# Startracker_Stepper.net
KiCad netlist of a schematic drawn in Altium Designer
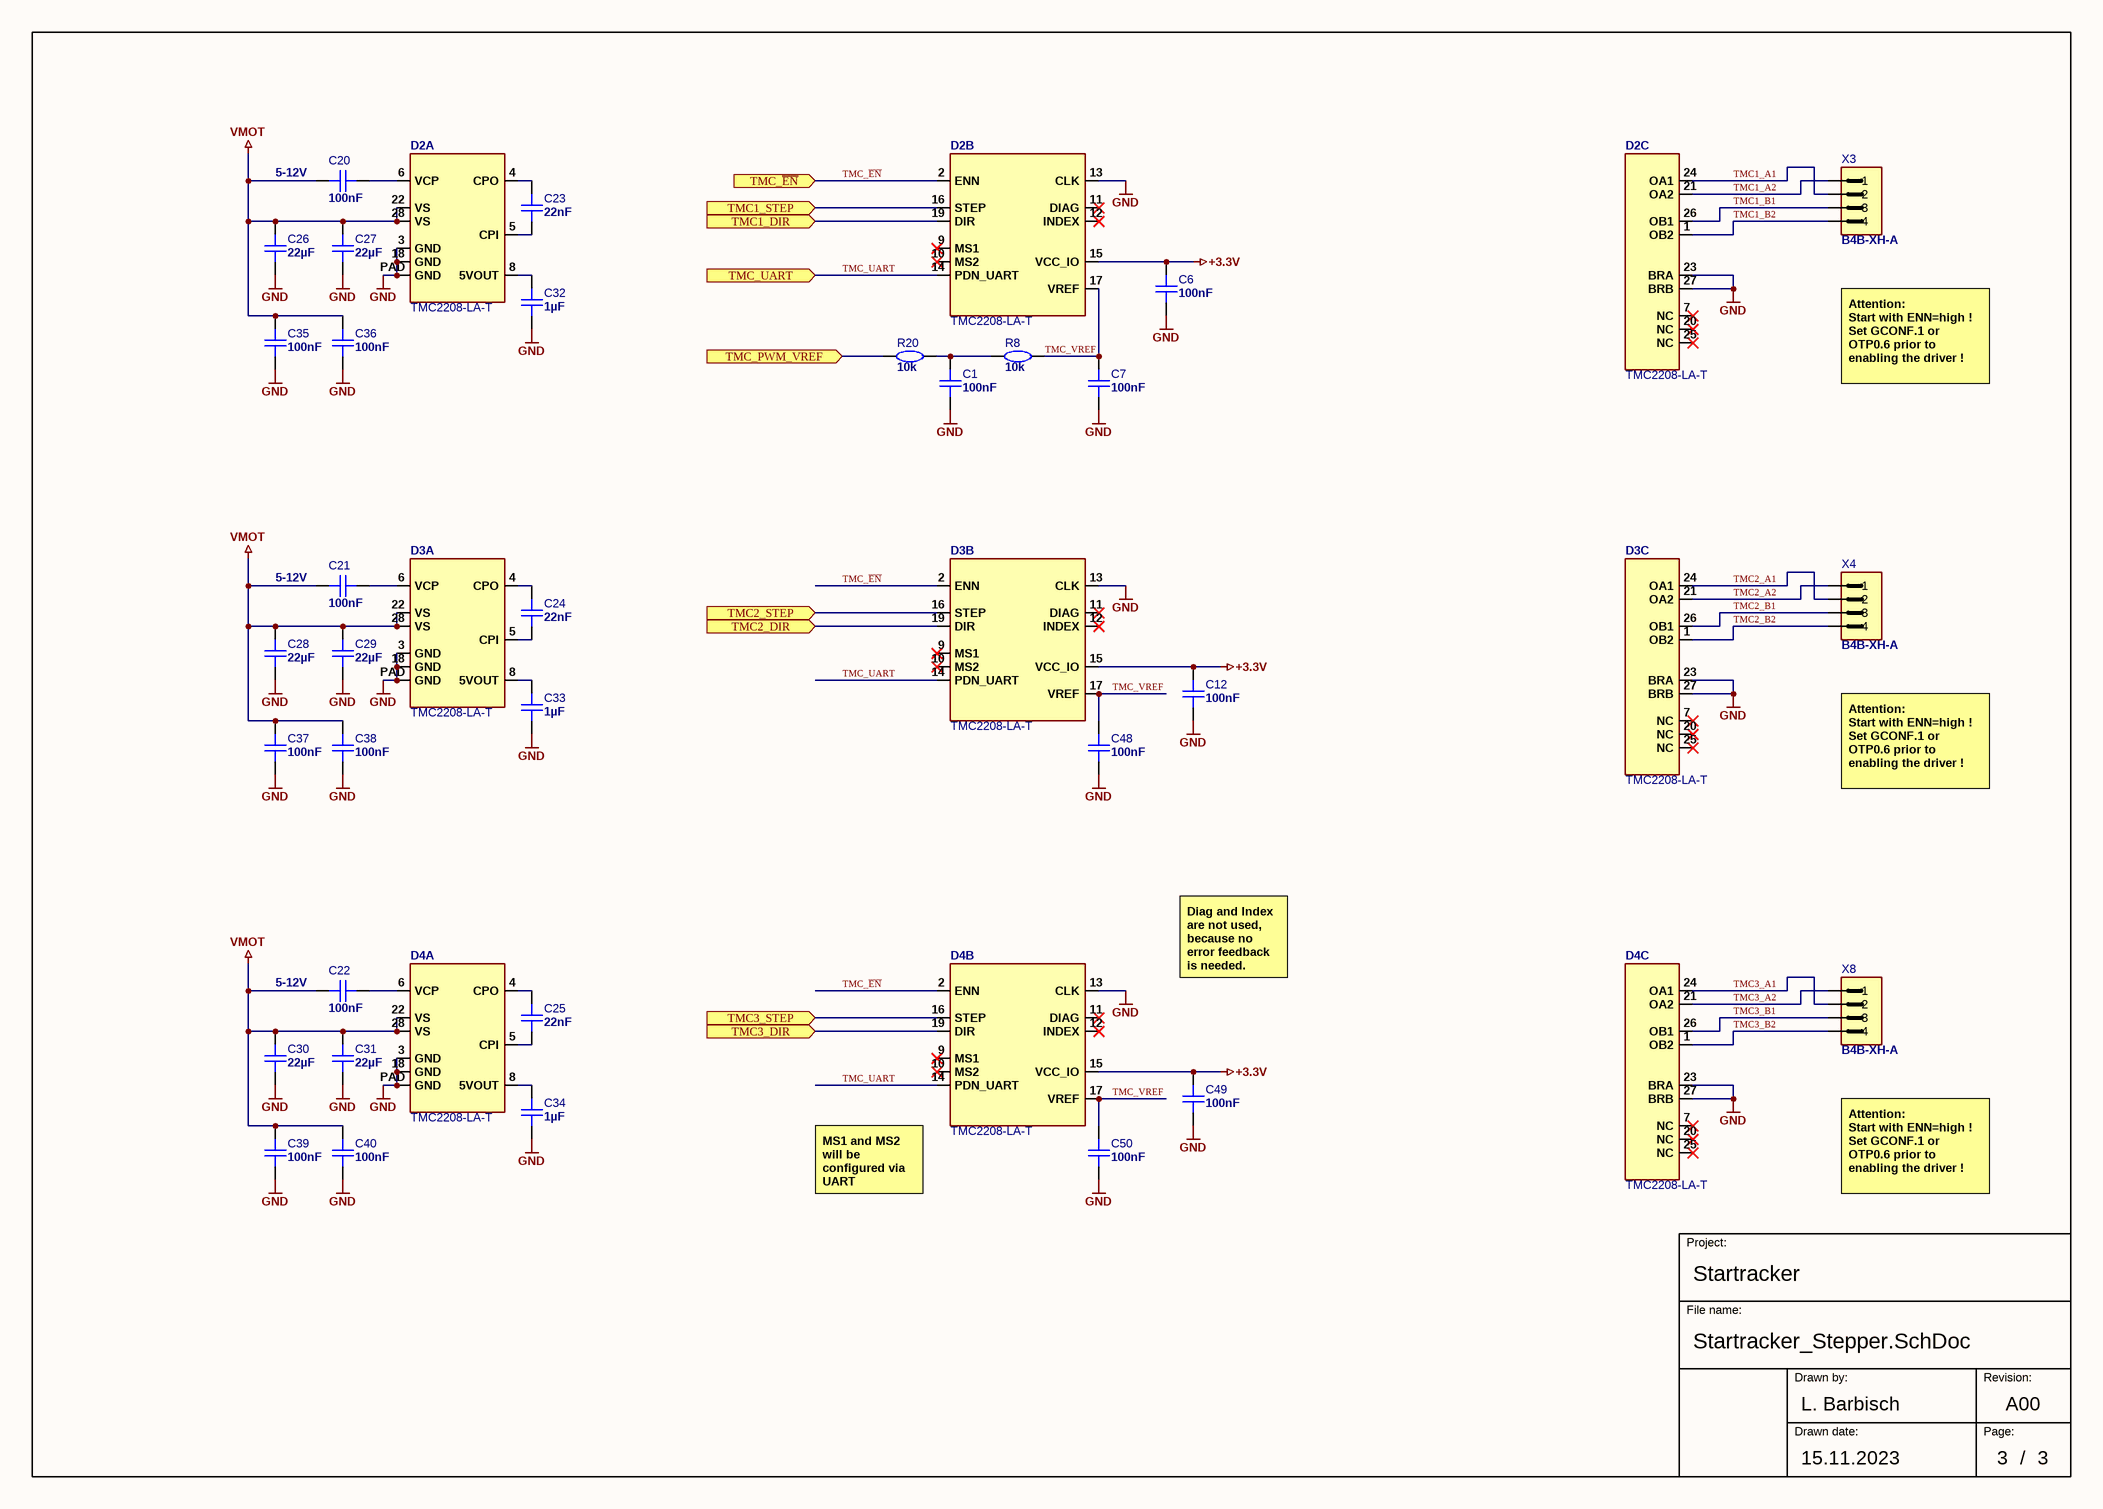
[diagram p0: Startracker_Stepper.SchDoc]

(export (version "E")
  (design (tool "Eeschema 10.0.6"))
  (components
    (comp (ref "C1")
      (value "100nF")
      (footprint "C-0603_1608_095_L_RF")
      (description "Cap Cer SMD 100n 50V 10% 0603 X7R")
      (fields
        (field (name "MANUFACTURER") "KEMET")
        (field (name "MANUFACTURER PART NUMBER") "C0603C104K5RAC")
        (field (name "USER") "epph")
      )
      (libsource (lib "GPV Switzerland SA") (part "CAP"))
    )
    (comp (ref "C6")
      (value "100nF")
      (footprint "C-0603_1608_095_L_RF")
      (description "Cap Cer SMD 100n 50V 10% 0603 X7R")
      (fields
        (field (name "MANUFACTURER") "KEMET")
        (field (name "MANUFACTURER PART NUMBER") "C0603C104K5RAC")
        (field (name "USER") "epph")
      )
      (libsource (lib "GPV Switzerland SA") (part "CAP"))
    )
    (comp (ref "C7")
      (value "100nF")
      (footprint "C-0603_1608_095_L_RF")
      (description "Cap Cer SMD 100n 50V 10% 0603 X7R")
      (fields
        (field (name "MANUFACTURER") "KEMET")
        (field (name "MANUFACTURER PART NUMBER") "C0603C104K5RAC")
        (field (name "USER") "epph")
      )
      (libsource (lib "GPV Switzerland SA") (part "CAP"))
    )
    (comp (ref "C12")
      (value "100nF")
      (footprint "C-0603_1608_095_L_RF")
      (description "Cap Cer SMD 100n 50V 10% 0603 X7R")
      (fields
        (field (name "MANUFACTURER") "KEMET")
        (field (name "MANUFACTURER PART NUMBER") "C0603C104K5RAC")
        (field (name "USER") "epph")
      )
      (libsource (lib "GPV Switzerland SA") (part "CAP"))
    )
    (comp (ref "C20")
      (value "100nF")
      (footprint "C-0603_1608_095_L_RF")
      (description "Cap Cer SMD 100n 50V 10% 0603 X7R")
      (fields
        (field (name "MANUFACTURER") "KEMET")
        (field (name "MANUFACTURER PART NUMBER") "C0603C104K5RAC")
        (field (name "USER") "epph")
      )
      (libsource (lib "GPV Switzerland SA") (part "CAP"))
    )
    (comp (ref "C21")
      (value "100nF")
      (footprint "C-0603_1608_095_L_RF")
      (description "Cap Cer SMD 100n 50V 10% 0603 X7R")
      (fields
        (field (name "MANUFACTURER") "KEMET")
        (field (name "MANUFACTURER PART NUMBER") "C0603C104K5RAC")
        (field (name "USER") "epph")
      )
      (libsource (lib "GPV Switzerland SA") (part "CAP"))
    )
    (comp (ref "C22")
      (value "100nF")
      (footprint "C-0603_1608_095_L_RF")
      (description "Cap Cer SMD 100n 50V 10% 0603 X7R")
      (fields
        (field (name "MANUFACTURER") "KEMET")
        (field (name "MANUFACTURER PART NUMBER") "C0603C104K5RAC")
        (field (name "USER") "epph")
      )
      (libsource (lib "GPV Switzerland SA") (part "CAP"))
    )
    (comp (ref "C23")
      (value "22nF")
      (footprint "C-0603_1608_095_L_RF")
      (description "Cap Cer SMD 22n 50V 10% 0603 X7R")
      (fields
        (field (name "MANUFACTURER PART NUMBER") "06035C223KAT*")
        (field (name "MANUFACTURER") "AVX")
        (field (name "USER") "zupa")
      )
      (libsource (lib "GPV Switzerland SA") (part "CAP"))
    )
    (comp (ref "C24")
      (value "22nF")
      (footprint "C-0603_1608_095_L_RF")
      (description "Cap Cer SMD 22n 50V 10% 0603 X7R")
      (fields
        (field (name "MANUFACTURER PART NUMBER") "06035C223KAT*")
        (field (name "MANUFACTURER") "AVX")
        (field (name "USER") "zupa")
      )
      (libsource (lib "GPV Switzerland SA") (part "CAP"))
    )
    (comp (ref "C25")
      (value "22nF")
      (footprint "C-0603_1608_095_L_RF")
      (description "Cap Cer SMD 22n 50V 10% 0603 X7R")
      (fields
        (field (name "MANUFACTURER PART NUMBER") "06035C223KAT*")
        (field (name "MANUFACTURER") "AVX")
        (field (name "USER") "zupa")
      )
      (libsource (lib "GPV Switzerland SA") (part "CAP"))
    )
    (comp (ref "C26")
      (value "22µF")
      (footprint "C-1206_3216_230_L_RF")
      (description "Cap Cer SMD 22u 25V 10% 1206 X5R")
      (fields
        (field (name "MANUFACTURER PART NUMBER") "GRM31CR61E226KE15*")
        (field (name "MANUFACTURER") "MURATA")
        (field (name "USER") "zupa")
      )
      (libsource (lib "GPV Switzerland SA") (part "CAP"))
    )
    (comp (ref "C27")
      (value "22µF")
      (footprint "C-1206_3216_230_L_RF")
      (description "Cap Cer SMD 22u 25V 10% 1206 X5R")
      (fields
        (field (name "MANUFACTURER PART NUMBER") "GRM31CR61E226KE15*")
        (field (name "MANUFACTURER") "MURATA")
        (field (name "USER") "zupa")
      )
      (libsource (lib "GPV Switzerland SA") (part "CAP"))
    )
    (comp (ref "C28")
      (value "22µF")
      (footprint "C-1206_3216_230_L_RF")
      (description "Cap Cer SMD 22u 25V 10% 1206 X5R")
      (fields
        (field (name "MANUFACTURER PART NUMBER") "GRM31CR61E226KE15*")
        (field (name "MANUFACTURER") "MURATA")
        (field (name "USER") "zupa")
      )
      (libsource (lib "GPV Switzerland SA") (part "CAP"))
    )
    (comp (ref "C29")
      (value "22µF")
      (footprint "C-1206_3216_230_L_RF")
      (description "Cap Cer SMD 22u 25V 10% 1206 X5R")
      (fields
        (field (name "MANUFACTURER PART NUMBER") "GRM31CR61E226KE15*")
        (field (name "MANUFACTURER") "MURATA")
        (field (name "USER") "zupa")
      )
      (libsource (lib "GPV Switzerland SA") (part "CAP"))
    )
    (comp (ref "C30")
      (value "22µF")
      (footprint "C-1206_3216_230_L_RF")
      (description "Cap Cer SMD 22u 25V 10% 1206 X5R")
      (fields
        (field (name "MANUFACTURER PART NUMBER") "GRM31CR61E226KE15*")
        (field (name "MANUFACTURER") "MURATA")
        (field (name "USER") "zupa")
      )
      (libsource (lib "GPV Switzerland SA") (part "CAP"))
    )
    (comp (ref "C31")
      (value "22µF")
      (footprint "C-1206_3216_230_L_RF")
      (description "Cap Cer SMD 22u 25V 10% 1206 X5R")
      (fields
        (field (name "MANUFACTURER PART NUMBER") "GRM31CR61E226KE15*")
        (field (name "MANUFACTURER") "MURATA")
        (field (name "USER") "zupa")
      )
      (libsource (lib "GPV Switzerland SA") (part "CAP"))
    )
    (comp (ref "C32")
      (value "1µF")
      (footprint "C-0603_1608_095_L_RF")
      (description "Cap Cer SMD 1u 16V 10% 0603 X7R")
      (fields
        (field (name "MANUFACTURER PART NUMBER") "0603YC105KAT*")
        (field (name "MANUFACTURER") "AVX")
        (field (name "USER") "zupa")
      )
      (libsource (lib "GPV Switzerland SA") (part "CAP"))
    )
    (comp (ref "C33")
      (value "1µF")
      (footprint "C-0603_1608_095_L_RF")
      (description "Cap Cer SMD 1u 16V 10% 0603 X7R")
      (fields
        (field (name "MANUFACTURER PART NUMBER") "0603YC105KAT*")
        (field (name "MANUFACTURER") "AVX")
        (field (name "USER") "zupa")
      )
      (libsource (lib "GPV Switzerland SA") (part "CAP"))
    )
    (comp (ref "C34")
      (value "1µF")
      (footprint "C-0603_1608_095_L_RF")
      (description "Cap Cer SMD 1u 16V 10% 0603 X7R")
      (fields
        (field (name "MANUFACTURER PART NUMBER") "0603YC105KAT*")
        (field (name "MANUFACTURER") "AVX")
        (field (name "USER") "zupa")
      )
      (libsource (lib "GPV Switzerland SA") (part "CAP"))
    )
    (comp (ref "C35")
      (value "100nF")
      (footprint "C-0603_1608_095_L_RF")
      (description "Cap Cer SMD 100n 50V 10% 0603 X7R")
      (fields
        (field (name "MANUFACTURER") "KEMET")
        (field (name "MANUFACTURER PART NUMBER") "C0603C104K5RAC")
        (field (name "USER") "epph")
      )
      (libsource (lib "GPV Switzerland SA") (part "CAP"))
    )
    (comp (ref "C36")
      (value "100nF")
      (footprint "C-0603_1608_095_L_RF")
      (description "Cap Cer SMD 100n 50V 10% 0603 X7R")
      (fields
        (field (name "MANUFACTURER") "KEMET")
        (field (name "MANUFACTURER PART NUMBER") "C0603C104K5RAC")
        (field (name "USER") "epph")
      )
      (libsource (lib "GPV Switzerland SA") (part "CAP"))
    )
    (comp (ref "C37")
      (value "100nF")
      (footprint "C-0603_1608_095_L_RF")
      (description "Cap Cer SMD 100n 50V 10% 0603 X7R")
      (fields
        (field (name "MANUFACTURER") "KEMET")
        (field (name "MANUFACTURER PART NUMBER") "C0603C104K5RAC")
        (field (name "USER") "epph")
      )
      (libsource (lib "GPV Switzerland SA") (part "CAP"))
    )
    (comp (ref "C38")
      (value "100nF")
      (footprint "C-0603_1608_095_L_RF")
      (description "Cap Cer SMD 100n 50V 10% 0603 X7R")
      (fields
        (field (name "MANUFACTURER") "KEMET")
        (field (name "MANUFACTURER PART NUMBER") "C0603C104K5RAC")
        (field (name "USER") "epph")
      )
      (libsource (lib "GPV Switzerland SA") (part "CAP"))
    )
    (comp (ref "C39")
      (value "100nF")
      (footprint "C-0603_1608_095_L_RF")
      (description "Cap Cer SMD 100n 50V 10% 0603 X7R")
      (fields
        (field (name "MANUFACTURER") "KEMET")
        (field (name "MANUFACTURER PART NUMBER") "C0603C104K5RAC")
        (field (name "USER") "epph")
      )
      (libsource (lib "GPV Switzerland SA") (part "CAP"))
    )
    (comp (ref "C40")
      (value "100nF")
      (footprint "C-0603_1608_095_L_RF")
      (description "Cap Cer SMD 100n 50V 10% 0603 X7R")
      (fields
        (field (name "MANUFACTURER") "KEMET")
        (field (name "MANUFACTURER PART NUMBER") "C0603C104K5RAC")
        (field (name "USER") "epph")
      )
      (libsource (lib "GPV Switzerland SA") (part "CAP"))
    )
    (comp (ref "C48")
      (value "100nF")
      (footprint "C-0603_1608_095_L_RF")
      (description "Cap Cer SMD 100n 50V 10% 0603 X7R")
      (fields
        (field (name "MANUFACTURER") "KEMET")
        (field (name "MANUFACTURER PART NUMBER") "C0603C104K5RAC")
        (field (name "USER") "epph")
      )
      (libsource (lib "GPV Switzerland SA") (part "CAP"))
    )
    (comp (ref "C49")
      (value "100nF")
      (footprint "C-0603_1608_095_L_RF")
      (description "Cap Cer SMD 100n 50V 10% 0603 X7R")
      (fields
        (field (name "MANUFACTURER") "KEMET")
        (field (name "MANUFACTURER PART NUMBER") "C0603C104K5RAC")
        (field (name "USER") "epph")
      )
      (libsource (lib "GPV Switzerland SA") (part "CAP"))
    )
    (comp (ref "C50")
      (value "100nF")
      (footprint "C-0603_1608_095_L_RF")
      (description "Cap Cer SMD 100n 50V 10% 0603 X7R")
      (fields
        (field (name "MANUFACTURER") "KEMET")
        (field (name "MANUFACTURER PART NUMBER") "C0603C104K5RAC")
        (field (name "USER") "epph")
      )
      (libsource (lib "GPV Switzerland SA") (part "CAP"))
    )
    (comp (ref "D2")
      (value "TMC2208-LA-T")
      (footprint "QFN28_N_RF")
      (description "IC DRIVER Stepper 1.4A")
      (fields (field (name "MANUFACTURER") "Analog Devices"))
      (libsource (lib "Global Library") (part "TMC2208-LA-T"))
    )
    (comp (ref "D3")
      (value "TMC2208-LA-T")
      (footprint "QFN28_N_RF")
      (description "IC DRIVER Stepper 1.4A")
      (fields (field (name "MANUFACTURER") "Analog Devices"))
      (libsource (lib "Global Library") (part "TMC2208-LA-T"))
    )
    (comp (ref "D4")
      (value "TMC2208-LA-T")
      (footprint "QFN28_N_RF")
      (description "IC DRIVER Stepper 1.4A")
      (fields (field (name "MANUFACTURER") "Analog Devices"))
      (libsource (lib "Global Library") (part "TMC2208-LA-T"))
    )
    (comp (ref "R8")
      (value "10k")
      (footprint "R-0603_1608_050_L_RF")
      (description "Res SMD 10k 1% 0.1W 0603")
      (fields
        (field (name "MANUFACTURER") "YAGEO")
        (field (name "MANUFACTURER PART NUMBER") "RC0603FR-0710KL")
        (field (name "USER") "zupa")
      )
      (libsource (lib "GPV Switzerland SA") (part "RES"))
    )
    (comp (ref "R20")
      (value "10k")
      (footprint "R-0603_1608_050_L_RF")
      (description "Res SMD 10k 1% 0.1W 0603")
      (fields
        (field (name "MANUFACTURER") "YAGEO")
        (field (name "MANUFACTURER PART NUMBER") "RC0603FR-0710KL")
        (field (name "USER") "zupa")
      )
      (libsource (lib "GPV Switzerland SA") (part "RES"))
    )
    (comp (ref "X3")
      (value "B4B-XH-A")
      (footprint "X-0124X0057-R_M04_P0250_JST_B4B-XH-A")
      (description "CONN HEADER  4POS_JST_B4B-XH")
      (fields
        (field (name "MANUFACTURER") "JST")
        (field (name "Comment") "CONN HEADER XH 4POS THT")
        (field (name "USER") "balu")
      )
      (libsource (lib "GPV Switzerland SA") (part "Connector-4P"))
    )
    (comp (ref "X4")
      (value "B4B-XH-A")
      (footprint "X-0124X0057-R_M04_P0250_JST_B4B-XH-A")
      (description "CONN HEADER  4POS_JST_B4B-XH")
      (fields
        (field (name "MANUFACTURER") "JST")
        (field (name "Comment") "CONN HEADER XH 4POS THT")
        (field (name "USER") "balu")
      )
      (libsource (lib "GPV Switzerland SA") (part "Connector-4P"))
    )
    (comp (ref "X8")
      (value "B4B-XH-A")
      (footprint "X-0124X0057-R_M04_P0250_JST_B4B-XH-A")
      (description "CONN HEADER  4POS_JST_B4B-XH")
      (fields
        (field (name "MANUFACTURER") "JST")
        (field (name "Comment") "CONN HEADER XH 4POS THT")
        (field (name "USER") "balu")
      )
      (libsource (lib "GPV Switzerland SA") (part "Connector-4P"))
    )
  )
  (nets
    (net (code "1") (name "+3.3V") (class "Default")
      (node (ref "C12") (pin "1") (pinfunction "1_1") (pintype "passive"))
      (node (ref "C49") (pin "1") (pinfunction "1_1") (pintype "passive"))
      (node (ref "C6") (pin "1") (pinfunction "1_1") (pintype "passive"))
      (node (ref "D2") (pin "15") (pinfunction "VCC_IO_15") (pintype "passive"))
      (node (ref "D3") (pin "15") (pinfunction "VCC_IO_15") (pintype "passive"))
      (node (ref "D4") (pin "15") (pinfunction "VCC_IO_15") (pintype "passive"))
    )
    (net (code "2") (name "/TMC1_A1") (class "Default")
      (node (ref "D2") (pin "24") (pinfunction "OA1_24") (pintype "passive"))
      (node (ref "X3") (pin "2") (pinfunction "2_2") (pintype "passive"))
    )
    (net (code "3") (name "/TMC1_A2") (class "Default")
      (node (ref "D2") (pin "21") (pinfunction "OA2_21") (pintype "passive"))
      (node (ref "X3") (pin "1") (pinfunction "1_1") (pintype "passive"))
    )
    (net (code "4") (name "/TMC1_B1") (class "Default")
      (node (ref "D2") (pin "26") (pinfunction "OB1_26") (pintype "passive"))
      (node (ref "X3") (pin "3") (pinfunction "3_3") (pintype "passive"))
    )
    (net (code "5") (name "/TMC1_B2") (class "Default")
      (node (ref "D2") (pin "1") (pinfunction "OB2_1") (pintype "passive"))
      (node (ref "X3") (pin "4") (pinfunction "4_4") (pintype "passive"))
    )
    (net (code "6") (name "/TMC1_DIR") (class "Default")
      (node (ref "D2") (pin "19") (pinfunction "DIR_19") (pintype "passive"))
    )
    (net (code "7") (name "/TMC1_STEP") (class "Default")
      (node (ref "D2") (pin "16") (pinfunction "STEP_16") (pintype "passive"))
    )
    (net (code "8") (name "/TMC2_A1") (class "Default")
      (node (ref "D3") (pin "24") (pinfunction "OA1_24") (pintype "passive"))
      (node (ref "X4") (pin "2") (pinfunction "2_2") (pintype "passive"))
    )
    (net (code "9") (name "/TMC2_A2") (class "Default")
      (node (ref "D3") (pin "21") (pinfunction "OA2_21") (pintype "passive"))
      (node (ref "X4") (pin "1") (pinfunction "1_1") (pintype "passive"))
    )
    (net (code "10") (name "/TMC2_B1") (class "Default")
      (node (ref "D3") (pin "26") (pinfunction "OB1_26") (pintype "passive"))
      (node (ref "X4") (pin "3") (pinfunction "3_3") (pintype "passive"))
    )
    (net (code "11") (name "/TMC2_B2") (class "Default")
      (node (ref "D3") (pin "1") (pinfunction "OB2_1") (pintype "passive"))
      (node (ref "X4") (pin "4") (pinfunction "4_4") (pintype "passive"))
    )
    (net (code "12") (name "/TMC2_DIR") (class "Default")
      (node (ref "D3") (pin "19") (pinfunction "DIR_19") (pintype "passive"))
    )
    (net (code "13") (name "/TMC2_STEP") (class "Default")
      (node (ref "D3") (pin "16") (pinfunction "STEP_16") (pintype "passive"))
    )
    (net (code "14") (name "/TMC3_A1") (class "Default")
      (node (ref "D4") (pin "24") (pinfunction "OA1_24") (pintype "passive"))
      (node (ref "X8") (pin "2") (pinfunction "2_2") (pintype "passive"))
    )
    (net (code "15") (name "/TMC3_A2") (class "Default")
      (node (ref "D4") (pin "21") (pinfunction "OA2_21") (pintype "passive"))
      (node (ref "X8") (pin "1") (pinfunction "1_1") (pintype "passive"))
    )
    (net (code "16") (name "/TMC3_B1") (class "Default")
      (node (ref "D4") (pin "26") (pinfunction "OB1_26") (pintype "passive"))
      (node (ref "X8") (pin "3") (pinfunction "3_3") (pintype "passive"))
    )
    (net (code "17") (name "/TMC3_B2") (class "Default")
      (node (ref "D4") (pin "1") (pinfunction "OB2_1") (pintype "passive"))
      (node (ref "X8") (pin "4") (pinfunction "4_4") (pintype "passive"))
    )
    (net (code "18") (name "/TMC3_DIR") (class "Default")
      (node (ref "D4") (pin "19") (pinfunction "DIR_19") (pintype "passive"))
    )
    (net (code "19") (name "/TMC3_STEP") (class "Default")
      (node (ref "D4") (pin "16") (pinfunction "STEP_16") (pintype "passive"))
    )
    (net (code "20") (name "/TMC_PWM_VREF") (class "Default")
      (node (ref "R20") (pin "1") (pinfunction "1_1") (pintype "passive"))
    )
    (net (code "21") (name "/TMC_UART") (class "Default")
      (node (ref "D2") (pin "14") (pinfunction "PDN_UART_14") (pintype "passive"))
      (node (ref "D3") (pin "14") (pinfunction "PDN_UART_14") (pintype "passive"))
      (node (ref "D4") (pin "14") (pinfunction "PDN_UART_14") (pintype "passive"))
    )
    (net (code "22") (name "/TMC_VREF") (class "Default")
      (node (ref "C48") (pin "1") (pinfunction "1_1") (pintype "passive"))
      (node (ref "C50") (pin "1") (pinfunction "1_1") (pintype "passive"))
      (node (ref "C7") (pin "1") (pinfunction "1_1") (pintype "passive"))
      (node (ref "D2") (pin "17") (pinfunction "VREF_17") (pintype "passive"))
      (node (ref "D3") (pin "17") (pinfunction "VREF_17") (pintype "passive"))
      (node (ref "D4") (pin "17") (pinfunction "VREF_17") (pintype "passive"))
      (node (ref "R8") (pin "2") (pinfunction "2_2") (pintype "passive"))
    )
    (net (code "23") (name "/TMC_~{EN}") (class "Default")
      (node (ref "D2") (pin "2") (pinfunction "ENN_2") (pintype "passive"))
      (node (ref "D3") (pin "2") (pinfunction "ENN_2") (pintype "passive"))
      (node (ref "D4") (pin "2") (pinfunction "ENN_2") (pintype "passive"))
    )
    (net (code "24") (name "GND") (class "Default")
      (node (ref "C1") (pin "2") (pinfunction "2_2") (pintype "passive"))
      (node (ref "C12") (pin "2") (pinfunction "2_2") (pintype "passive"))
      (node (ref "C26") (pin "1") (pinfunction "1_1") (pintype "passive"))
      (node (ref "C27") (pin "1") (pinfunction "1_1") (pintype "passive"))
      (node (ref "C28") (pin "1") (pinfunction "1_1") (pintype "passive"))
      (node (ref "C29") (pin "1") (pinfunction "1_1") (pintype "passive"))
      (node (ref "C30") (pin "1") (pinfunction "1_1") (pintype "passive"))
      (node (ref "C31") (pin "1") (pinfunction "1_1") (pintype "passive"))
      (node (ref "C32") (pin "1") (pinfunction "1_1") (pintype "passive"))
      (node (ref "C33") (pin "1") (pinfunction "1_1") (pintype "passive"))
      (node (ref "C34") (pin "1") (pinfunction "1_1") (pintype "passive"))
      (node (ref "C35") (pin "1") (pinfunction "1_1") (pintype "passive"))
      (node (ref "C36") (pin "1") (pinfunction "1_1") (pintype "passive"))
      (node (ref "C37") (pin "1") (pinfunction "1_1") (pintype "passive"))
      (node (ref "C38") (pin "1") (pinfunction "1_1") (pintype "passive"))
      (node (ref "C39") (pin "1") (pinfunction "1_1") (pintype "passive"))
      (node (ref "C40") (pin "1") (pinfunction "1_1") (pintype "passive"))
      (node (ref "C48") (pin "2") (pinfunction "2_2") (pintype "passive"))
      (node (ref "C49") (pin "2") (pinfunction "2_2") (pintype "passive"))
      (node (ref "C50") (pin "2") (pinfunction "2_2") (pintype "passive"))
      (node (ref "C6") (pin "2") (pinfunction "2_2") (pintype "passive"))
      (node (ref "C7") (pin "2") (pinfunction "2_2") (pintype "passive"))
      (node (ref "D2") (pin "13") (pinfunction "CLK_13") (pintype "passive"))
      (node (ref "D2") (pin "18") (pinfunction "GND_18") (pintype "passive"))
      (node (ref "D2") (pin "23") (pinfunction "BRA_23") (pintype "passive"))
      (node (ref "D2") (pin "27") (pinfunction "BRB_27") (pintype "passive"))
      (node (ref "D2") (pin "3") (pinfunction "GND_3") (pintype "passive"))
      (node (ref "D2") (pin "PAD") (pinfunction "GND_PAD") (pintype "passive"))
      (node (ref "D3") (pin "13") (pinfunction "CLK_13") (pintype "passive"))
      (node (ref "D3") (pin "18") (pinfunction "GND_18") (pintype "passive"))
      (node (ref "D3") (pin "23") (pinfunction "BRA_23") (pintype "passive"))
      (node (ref "D3") (pin "27") (pinfunction "BRB_27") (pintype "passive"))
      (node (ref "D3") (pin "3") (pinfunction "GND_3") (pintype "passive"))
      (node (ref "D3") (pin "PAD") (pinfunction "GND_PAD") (pintype "passive"))
      (node (ref "D4") (pin "13") (pinfunction "CLK_13") (pintype "passive"))
      (node (ref "D4") (pin "18") (pinfunction "GND_18") (pintype "passive"))
      (node (ref "D4") (pin "23") (pinfunction "BRA_23") (pintype "passive"))
      (node (ref "D4") (pin "27") (pinfunction "BRB_27") (pintype "passive"))
      (node (ref "D4") (pin "3") (pinfunction "GND_3") (pintype "passive"))
      (node (ref "D4") (pin "PAD") (pinfunction "GND_PAD") (pintype "passive"))
    )
    (net (code "25") (name "Net-(C1-Pad1)") (class "Default")
      (node (ref "C1") (pin "1") (pinfunction "1_1") (pintype "passive"))
      (node (ref "R20") (pin "2") (pinfunction "2_2") (pintype "passive"))
      (node (ref "R8") (pin "1") (pinfunction "1_1") (pintype "passive"))
    )
    (net (code "26") (name "Net-(D2A-5VOUT)") (class "Default")
      (node (ref "C32") (pin "2") (pinfunction "2_2") (pintype "passive"))
      (node (ref "D2") (pin "8") (pinfunction "5VOUT_8") (pintype "passive"))
    )
    (net (code "27") (name "Net-(D2A-CPI)") (class "Default")
      (node (ref "C23") (pin "1") (pinfunction "1_1") (pintype "passive"))
      (node (ref "D2") (pin "5") (pinfunction "CPI_5") (pintype "passive"))
    )
    (net (code "28") (name "Net-(D2A-CPO)") (class "Default")
      (node (ref "C23") (pin "2") (pinfunction "2_2") (pintype "passive"))
      (node (ref "D2") (pin "4") (pinfunction "CPO_4") (pintype "passive"))
    )
    (net (code "29") (name "Net-(D2A-VCP)") (class "Default")
      (node (ref "C20") (pin "1") (pinfunction "1_1") (pintype "passive"))
      (node (ref "D2") (pin "6") (pinfunction "VCP_6") (pintype "passive"))
    )
    (net (code "30") (name "Net-(D3A-5VOUT)") (class "Default")
      (node (ref "C33") (pin "2") (pinfunction "2_2") (pintype "passive"))
      (node (ref "D3") (pin "8") (pinfunction "5VOUT_8") (pintype "passive"))
    )
    (net (code "31") (name "Net-(D3A-CPI)") (class "Default")
      (node (ref "C24") (pin "1") (pinfunction "1_1") (pintype "passive"))
      (node (ref "D3") (pin "5") (pinfunction "CPI_5") (pintype "passive"))
    )
    (net (code "32") (name "Net-(D3A-CPO)") (class "Default")
      (node (ref "C24") (pin "2") (pinfunction "2_2") (pintype "passive"))
      (node (ref "D3") (pin "4") (pinfunction "CPO_4") (pintype "passive"))
    )
    (net (code "33") (name "Net-(D3A-VCP)") (class "Default")
      (node (ref "C21") (pin "1") (pinfunction "1_1") (pintype "passive"))
      (node (ref "D3") (pin "6") (pinfunction "VCP_6") (pintype "passive"))
    )
    (net (code "34") (name "Net-(D4A-5VOUT)") (class "Default")
      (node (ref "C34") (pin "2") (pinfunction "2_2") (pintype "passive"))
      (node (ref "D4") (pin "8") (pinfunction "5VOUT_8") (pintype "passive"))
    )
    (net (code "35") (name "Net-(D4A-CPI)") (class "Default")
      (node (ref "C25") (pin "1") (pinfunction "1_1") (pintype "passive"))
      (node (ref "D4") (pin "5") (pinfunction "CPI_5") (pintype "passive"))
    )
    (net (code "36") (name "Net-(D4A-CPO)") (class "Default")
      (node (ref "C25") (pin "2") (pinfunction "2_2") (pintype "passive"))
      (node (ref "D4") (pin "4") (pinfunction "CPO_4") (pintype "passive"))
    )
    (net (code "37") (name "Net-(D4A-VCP)") (class "Default")
      (node (ref "C22") (pin "1") (pinfunction "1_1") (pintype "passive"))
      (node (ref "D4") (pin "6") (pinfunction "VCP_6") (pintype "passive"))
    )
    (net (code "38") (name "VMOT") (class "Default")
      (node (ref "C20") (pin "2") (pinfunction "2_2") (pintype "passive"))
      (node (ref "C21") (pin "2") (pinfunction "2_2") (pintype "passive"))
      (node (ref "C22") (pin "2") (pinfunction "2_2") (pintype "passive"))
      (node (ref "C26") (pin "2") (pinfunction "2_2") (pintype "passive"))
      (node (ref "C27") (pin "2") (pinfunction "2_2") (pintype "passive"))
      (node (ref "C28") (pin "2") (pinfunction "2_2") (pintype "passive"))
      (node (ref "C29") (pin "2") (pinfunction "2_2") (pintype "passive"))
      (node (ref "C30") (pin "2") (pinfunction "2_2") (pintype "passive"))
      (node (ref "C31") (pin "2") (pinfunction "2_2") (pintype "passive"))
      (node (ref "C35") (pin "2") (pinfunction "2_2") (pintype "passive"))
      (node (ref "C36") (pin "2") (pinfunction "2_2") (pintype "passive"))
      (node (ref "C37") (pin "2") (pinfunction "2_2") (pintype "passive"))
      (node (ref "C38") (pin "2") (pinfunction "2_2") (pintype "passive"))
      (node (ref "C39") (pin "2") (pinfunction "2_2") (pintype "passive"))
      (node (ref "C40") (pin "2") (pinfunction "2_2") (pintype "passive"))
      (node (ref "D2") (pin "22") (pinfunction "VS_22") (pintype "passive"))
      (node (ref "D2") (pin "28") (pinfunction "VS_28") (pintype "passive"))
      (node (ref "D3") (pin "22") (pinfunction "VS_22") (pintype "passive"))
      (node (ref "D3") (pin "28") (pinfunction "VS_28") (pintype "passive"))
      (node (ref "D4") (pin "22") (pinfunction "VS_22") (pintype "passive"))
      (node (ref "D4") (pin "28") (pinfunction "VS_28") (pintype "passive"))
    )
    (net (code "39") (name "unconnected-(D2B-DIAG-Pad11)") (class "Default")
      (node (ref "D2") (pin "11") (pinfunction "DIAG_11") (pintype "passive+no_connect"))
    )
    (net (code "40") (name "unconnected-(D2B-INDEX-Pad12)") (class "Default")
      (node (ref "D2") (pin "12") (pinfunction "INDEX_12") (pintype "passive+no_connect"))
    )
    (net (code "41") (name "unconnected-(D2B-MS1-Pad9)") (class "Default")
      (node (ref "D2") (pin "9") (pinfunction "MS1_9") (pintype "passive+no_connect"))
    )
    (net (code "42") (name "unconnected-(D2B-MS2-Pad10)") (class "Default")
      (node (ref "D2") (pin "10") (pinfunction "MS2_10") (pintype "passive+no_connect"))
    )
    (net (code "43") (name "unconnected-(D2C-NC-Pad7)") (class "Default")
      (node (ref "D2") (pin "7") (pinfunction "NC_7") (pintype "passive+no_connect"))
    )
    (net (code "44") (name "unconnected-(D2C-NC-Pad20)") (class "Default")
      (node (ref "D2") (pin "20") (pinfunction "NC_20") (pintype "passive+no_connect"))
    )
    (net (code "45") (name "unconnected-(D2C-NC-Pad25)") (class "Default")
      (node (ref "D2") (pin "25") (pinfunction "NC_25") (pintype "passive+no_connect"))
    )
    (net (code "46") (name "unconnected-(D3B-DIAG-Pad11)") (class "Default")
      (node (ref "D3") (pin "11") (pinfunction "DIAG_11") (pintype "passive+no_connect"))
    )
    (net (code "47") (name "unconnected-(D3B-INDEX-Pad12)") (class "Default")
      (node (ref "D3") (pin "12") (pinfunction "INDEX_12") (pintype "passive+no_connect"))
    )
    (net (code "48") (name "unconnected-(D3B-MS1-Pad9)") (class "Default")
      (node (ref "D3") (pin "9") (pinfunction "MS1_9") (pintype "passive+no_connect"))
    )
    (net (code "49") (name "unconnected-(D3B-MS2-Pad10)") (class "Default")
      (node (ref "D3") (pin "10") (pinfunction "MS2_10") (pintype "passive+no_connect"))
    )
    (net (code "50") (name "unconnected-(D3C-NC-Pad7)") (class "Default")
      (node (ref "D3") (pin "7") (pinfunction "NC_7") (pintype "passive+no_connect"))
    )
    (net (code "51") (name "unconnected-(D3C-NC-Pad20)") (class "Default")
      (node (ref "D3") (pin "20") (pinfunction "NC_20") (pintype "passive+no_connect"))
    )
    (net (code "52") (name "unconnected-(D3C-NC-Pad25)") (class "Default")
      (node (ref "D3") (pin "25") (pinfunction "NC_25") (pintype "passive+no_connect"))
    )
    (net (code "53") (name "unconnected-(D4B-DIAG-Pad11)") (class "Default")
      (node (ref "D4") (pin "11") (pinfunction "DIAG_11") (pintype "passive+no_connect"))
    )
    (net (code "54") (name "unconnected-(D4B-INDEX-Pad12)") (class "Default")
      (node (ref "D4") (pin "12") (pinfunction "INDEX_12") (pintype "passive+no_connect"))
    )
    (net (code "55") (name "unconnected-(D4B-MS1-Pad9)") (class "Default")
      (node (ref "D4") (pin "9") (pinfunction "MS1_9") (pintype "passive+no_connect"))
    )
    (net (code "56") (name "unconnected-(D4B-MS2-Pad10)") (class "Default")
      (node (ref "D4") (pin "10") (pinfunction "MS2_10") (pintype "passive+no_connect"))
    )
    (net (code "57") (name "unconnected-(D4C-NC-Pad7)") (class "Default")
      (node (ref "D4") (pin "7") (pinfunction "NC_7") (pintype "passive+no_connect"))
    )
    (net (code "58") (name "unconnected-(D4C-NC-Pad20)") (class "Default")
      (node (ref "D4") (pin "20") (pinfunction "NC_20") (pintype "passive+no_connect"))
    )
    (net (code "59") (name "unconnected-(D4C-NC-Pad25)") (class "Default")
      (node (ref "D4") (pin "25") (pinfunction "NC_25") (pintype "passive+no_connect"))
    )
  )
)
